# R2Quad_Power_Distribution_Board.net
KiCad netlist of a schematic drawn in EAGLE
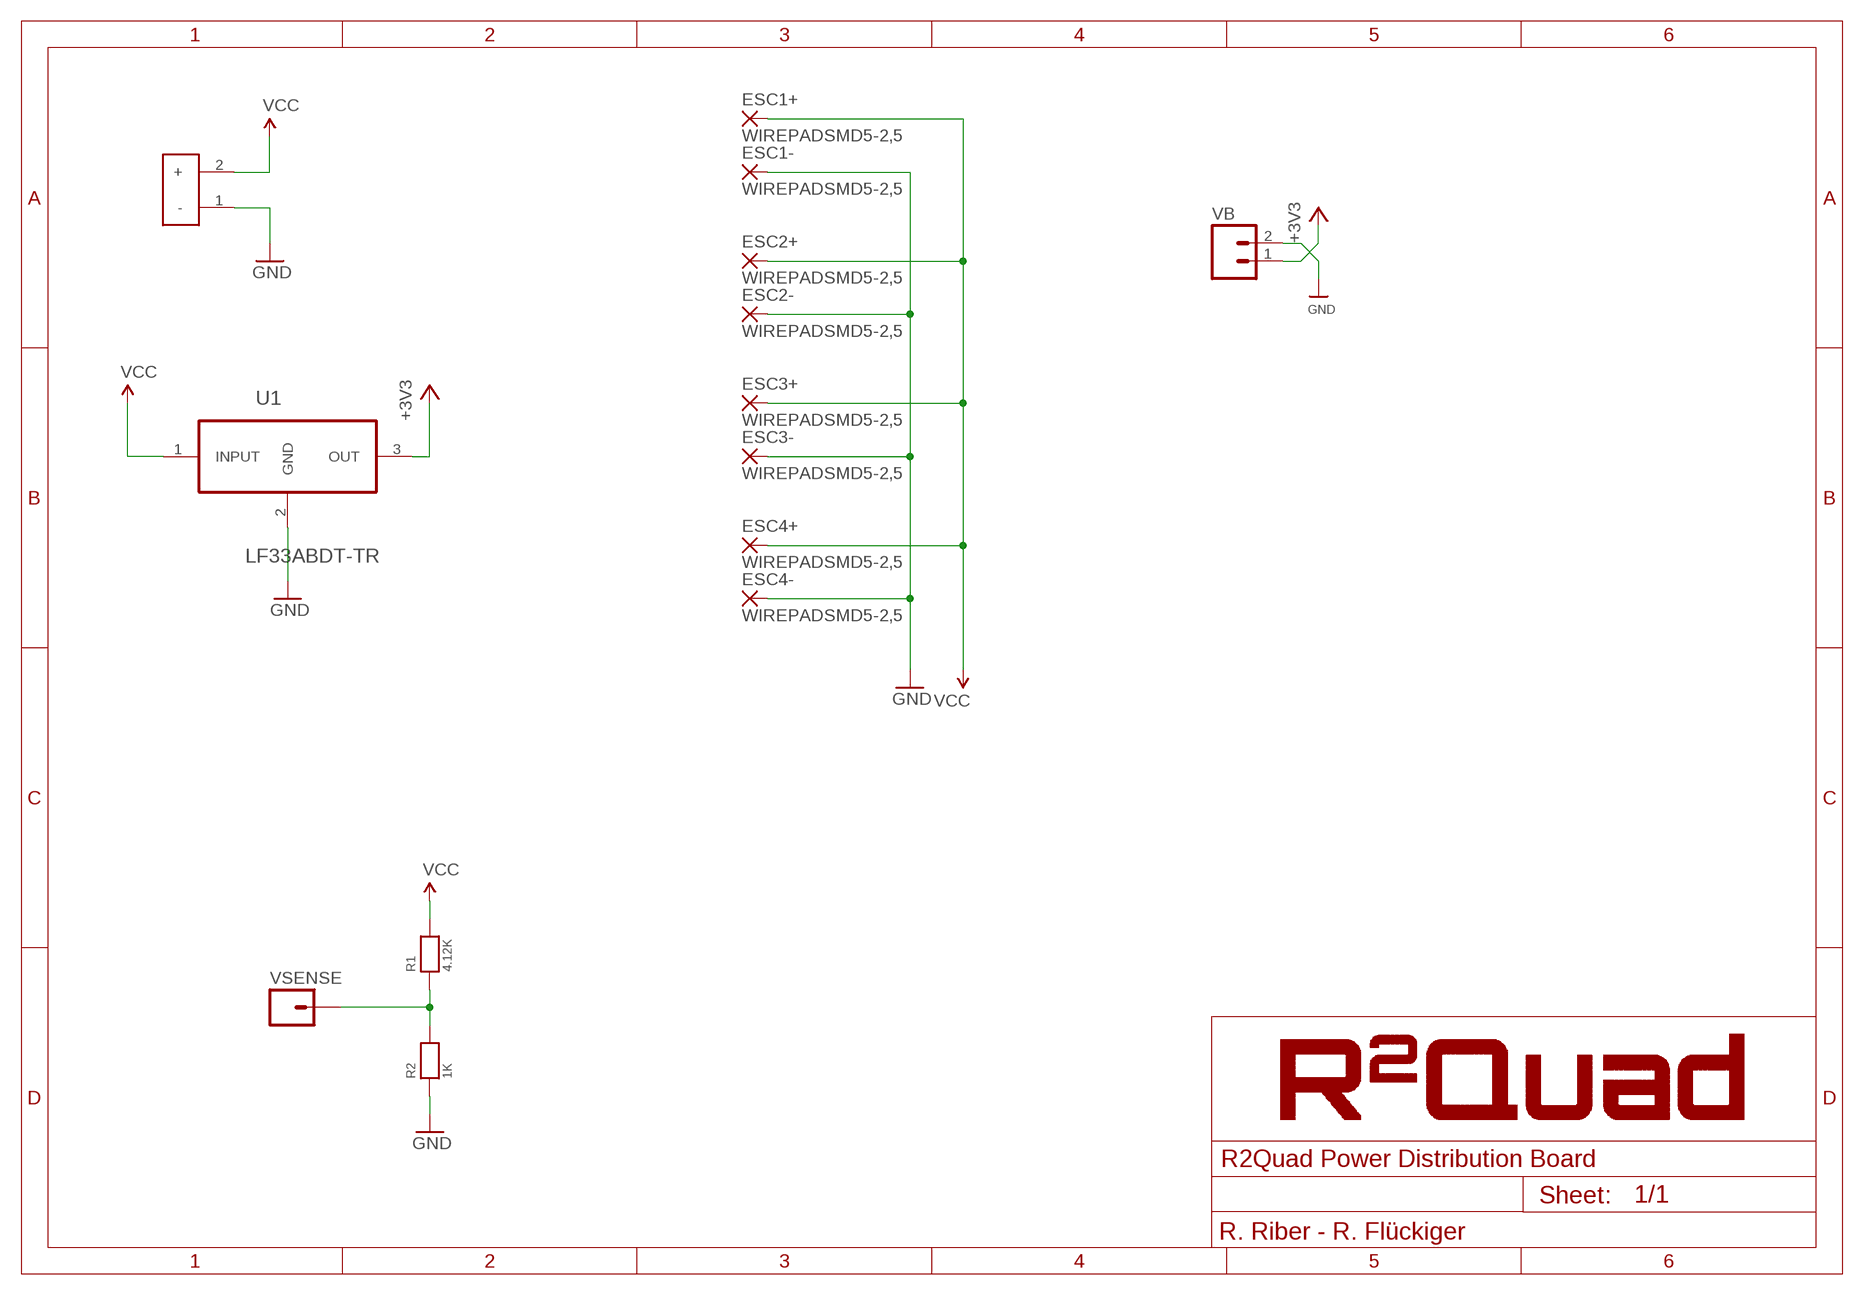
[diagram p0: schematic, sheet 1]

(export (version "E")
  (design (tool "Eeschema 10.0.6"))
  (components
    (comp (ref "ESC1+")
      (value "WIREPADSMD5-2,5")
      (footprint "eagle-import:5-2,5")
      (libsource (lib "eagle-import") (part "WIREPADSMD5-2,5"))
    )
    (comp (ref "ESC1-")
      (value "WIREPADSMD5-2,5")
      (footprint "eagle-import:5-2,5")
      (libsource (lib "eagle-import") (part "WIREPADSMD5-2,5"))
    )
    (comp (ref "ESC2+")
      (value "WIREPADSMD5-2,5")
      (footprint "eagle-import:5-2,5")
      (libsource (lib "eagle-import") (part "WIREPADSMD5-2,5"))
    )
    (comp (ref "ESC2-")
      (value "WIREPADSMD5-2,5")
      (footprint "eagle-import:5-2,5")
      (libsource (lib "eagle-import") (part "WIREPADSMD5-2,5"))
    )
    (comp (ref "ESC3+")
      (value "WIREPADSMD5-2,5")
      (footprint "eagle-import:5-2,5")
      (libsource (lib "eagle-import") (part "WIREPADSMD5-2,5"))
    )
    (comp (ref "ESC3-")
      (value "WIREPADSMD5-2,5")
      (footprint "eagle-import:5-2,5")
      (libsource (lib "eagle-import") (part "WIREPADSMD5-2,5"))
    )
    (comp (ref "ESC4+")
      (value "WIREPADSMD5-2,5")
      (footprint "eagle-import:5-2,5")
      (libsource (lib "eagle-import") (part "WIREPADSMD5-2,5"))
    )
    (comp (ref "ESC4-")
      (value "WIREPADSMD5-2,5")
      (footprint "eagle-import:5-2,5")
      (libsource (lib "eagle-import") (part "WIREPADSMD5-2,5"))
    )
    (comp (ref "R1")
      (value "4.12K")
      (footprint "eagle-import:0603")
      (libsource (lib "eagle-import") (part "RESISTOR0603"))
    )
    (comp (ref "R2")
      (value "1K")
      (footprint "eagle-import:0603")
      (libsource (lib "eagle-import") (part "RESISTOR0603"))
    )
    (comp (ref "U$1")
      (value "XT60")
      (footprint "eagle-import:XT60")
      (libsource (lib "eagle-import") (part "XT60"))
    )
    (comp (ref "U1")
      (value "LF33ABDT-TR")
      (footprint "eagle-import:TO228P972X240-3N")
      (fields (field (name "MF") "STMicroelectronics"))
      (libsource (lib "eagle-import") (part "LF33ABDT-TR"))
    )
    (comp (ref "VB")
      (value "M02PTH")
      (footprint "eagle-import:1X02")
      (libsource (lib "eagle-import") (part "M02PTH"))
    )
    (comp (ref "VSENSE")
      (value "M01PTH")
      (footprint "eagle-import:1X01")
      (libsource (lib "eagle-import") (part "M01PTH"))
    )
  )
  (nets
    (net (code "1") (name "+3V3") (class "Default")
      (node (ref "U1") (pin "3") (pinfunction "OUT_3") (pintype "output"))
      (node (ref "VB") (pin "1") (pinfunction "1_1") (pintype "passive"))
    )
    (net (code "2") (name "GND") (class "Default")
      (node (ref "ESC1-") (pin "1") (pinfunction "P_1") (pintype "passive"))
      (node (ref "ESC2-") (pin "1") (pinfunction "P_1") (pintype "passive"))
      (node (ref "ESC3-") (pin "1") (pinfunction "P_1") (pintype "passive"))
      (node (ref "ESC4-") (pin "1") (pinfunction "P_1") (pintype "passive"))
      (node (ref "R2") (pin "1") (pinfunction "1_1") (pintype "passive"))
      (node (ref "U$1") (pin "1") (pinfunction "-_1") (pintype "bidirectional"))
      (node (ref "U1") (pin "2") (pinfunction "GND_2") (pintype "passive"))
      (node (ref "VB") (pin "2") (pinfunction "2_2") (pintype "passive"))
    )
    (net (code "3") (name "Net-(R1-Pad1)") (class "Default")
      (node (ref "R1") (pin "1") (pinfunction "1_1") (pintype "passive"))
      (node (ref "R2") (pin "2") (pinfunction "2_2") (pintype "passive"))
      (node (ref "VSENSE") (pin "1") (pinfunction "1_1") (pintype "passive"))
    )
    (net (code "4") (name "VCC") (class "Default")
      (node (ref "ESC1+") (pin "1") (pinfunction "P_1") (pintype "passive"))
      (node (ref "ESC2+") (pin "1") (pinfunction "P_1") (pintype "passive"))
      (node (ref "ESC3+") (pin "1") (pinfunction "P_1") (pintype "passive"))
      (node (ref "ESC4+") (pin "1") (pinfunction "P_1") (pintype "passive"))
      (node (ref "R1") (pin "2") (pinfunction "2_2") (pintype "passive"))
      (node (ref "U$1") (pin "2") (pinfunction "+_2") (pintype "bidirectional"))
      (node (ref "U1") (pin "1") (pinfunction "INPUT_1") (pintype "input"))
    )
  )
)
